# MCU_DBG.net
KiCad netlist of a schematic drawn in Altium Designer
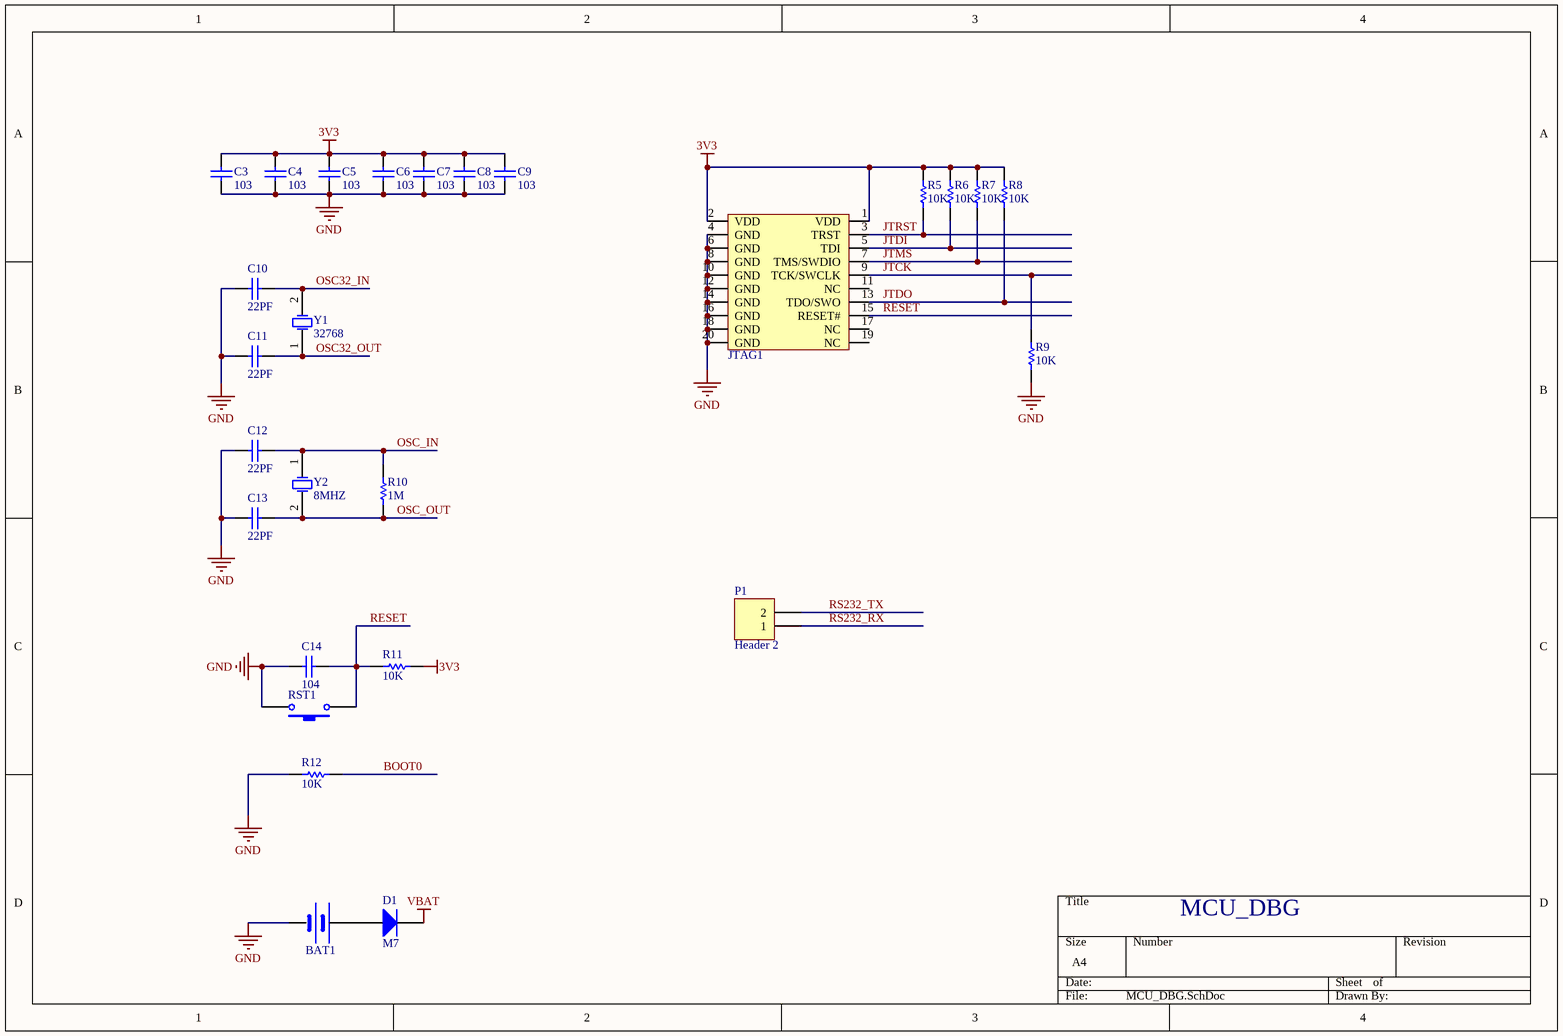
[diagram p0: MCU_DBG.SchDoc]

(export (version "E")
  (design (tool "Eeschema 10.0.6"))
  (components
    (comp (ref "BAT1")
      (value "BATT")
      (footprint "Bat2032")
      (libsource (lib "Integrated_Library_YZ") (part "BAT"))
    )
    (comp (ref "C3")
      (value "103")
      (footprint "RC0805")
      (description "Capacitor")
      (fields (field (name "Comment") "Cap") (field (name "PUBLISHER") "Altium Limited"))
      (libsource (lib "Miscellaneous Devices") (part "Cap"))
    )
    (comp (ref "C4")
      (value "103")
      (footprint "RC0805")
      (description "Capacitor")
      (fields (field (name "Comment") "Cap") (field (name "PUBLISHER") "Altium Limited"))
      (libsource (lib "Miscellaneous Devices") (part "Cap"))
    )
    (comp (ref "C5")
      (value "103")
      (footprint "RC0805")
      (description "Capacitor")
      (fields (field (name "Comment") "Cap") (field (name "PUBLISHER") "Altium Limited"))
      (libsource (lib "Miscellaneous Devices") (part "Cap"))
    )
    (comp (ref "C6")
      (value "103")
      (footprint "RC0805")
      (description "Capacitor")
      (fields (field (name "Comment") "Cap") (field (name "PUBLISHER") "Altium Limited"))
      (libsource (lib "Miscellaneous Devices") (part "Cap"))
    )
    (comp (ref "C7")
      (value "103")
      (footprint "RC0805")
      (description "Capacitor")
      (fields (field (name "Comment") "Cap") (field (name "PUBLISHER") "Altium Limited"))
      (libsource (lib "Miscellaneous Devices") (part "Cap"))
    )
    (comp (ref "C8")
      (value "103")
      (footprint "RC0805")
      (description "Capacitor")
      (fields (field (name "Comment") "Cap") (field (name "PUBLISHER") "Altium Limited"))
      (libsource (lib "Miscellaneous Devices") (part "Cap"))
    )
    (comp (ref "C9")
      (value "103")
      (footprint "RC0805")
      (description "Capacitor")
      (fields (field (name "Comment") "Cap") (field (name "PUBLISHER") "Altium Limited"))
      (libsource (lib "Miscellaneous Devices") (part "Cap"))
    )
    (comp (ref "C10")
      (value "22PF")
      (footprint "RC0805")
      (description "Capacitor")
      (fields (field (name "Comment") "Cap") (field (name "PUBLISHER") "Altium Limited"))
      (libsource (lib "Miscellaneous Devices") (part "Cap"))
    )
    (comp (ref "C11")
      (value "22PF")
      (footprint "RC0805")
      (description "Capacitor")
      (fields (field (name "Comment") "Cap") (field (name "PUBLISHER") "Altium Limited"))
      (libsource (lib "Miscellaneous Devices") (part "Cap"))
    )
    (comp (ref "C12")
      (value "22PF")
      (footprint "RC0805")
      (description "Capacitor")
      (fields (field (name "Comment") "Cap") (field (name "PUBLISHER") "Altium Limited"))
      (libsource (lib "Miscellaneous Devices") (part "Cap"))
    )
    (comp (ref "C13")
      (value "22PF")
      (footprint "RC0805")
      (description "Capacitor")
      (fields (field (name "Comment") "Cap") (field (name "PUBLISHER") "Altium Limited"))
      (libsource (lib "Miscellaneous Devices") (part "Cap"))
    )
    (comp (ref "C14")
      (value "104")
      (footprint "RC0805")
      (description "Capacitor")
      (fields (field (name "Comment") "Cap") (field (name "PUBLISHER") "Altium Limited"))
      (libsource (lib "Miscellaneous Devices") (part "Cap"))
    )
    (comp (ref "D1")
      (value "M7")
      (footprint "ss14")
      (description "Default Diode")
      (fields (field (name "PUBLISHER") "Altium Limited"))
      (libsource (lib "Miscellaneous Devices") (part "Diode"))
    )
    (comp (ref "JTAG1") (value "JTAG") (footprint "JTAG_20") (libsource (lib "底板封装库") (part "JTAG")))
    (comp (ref "P1")
      (value "Header 2")
      (footprint "HDR1X2")
      (description "Header, 2-Pin")
      (fields (field (name "PUBLISHER") "Altium Limited"))
      (libsource (lib "Miscellaneous Connectors") (part "Header 2"))
    )
    (comp (ref "R5")
      (value "10K")
      (footprint "RC0805")
      (description "Resistor")
      (fields (field (name "Comment") "Res1") (field (name "PUBLISHER") "Altium Limited"))
      (libsource (lib "Miscellaneous Devices") (part "Res1"))
    )
    (comp (ref "R6")
      (value "10K")
      (footprint "RC0805")
      (description "Resistor")
      (fields (field (name "Comment") "Res1") (field (name "PUBLISHER") "Altium Limited"))
      (libsource (lib "Miscellaneous Devices") (part "Res1"))
    )
    (comp (ref "R7")
      (value "10K")
      (footprint "RC0805")
      (description "Resistor")
      (fields (field (name "Comment") "Res1") (field (name "PUBLISHER") "Altium Limited"))
      (libsource (lib "Miscellaneous Devices") (part "Res1"))
    )
    (comp (ref "R8")
      (value "10K")
      (footprint "RC0805")
      (description "Resistor")
      (fields (field (name "Comment") "Res1") (field (name "PUBLISHER") "Altium Limited"))
      (libsource (lib "Miscellaneous Devices") (part "Res1"))
    )
    (comp (ref "R9")
      (value "10K")
      (footprint "RC0805")
      (description "Resistor")
      (fields (field (name "Comment") "Res1") (field (name "PUBLISHER") "Altium Limited"))
      (libsource (lib "Miscellaneous Devices") (part "Res1"))
    )
    (comp (ref "R10")
      (value "1M")
      (footprint "RC0805")
      (description "Resistor")
      (fields (field (name "Comment") "Res1") (field (name "PUBLISHER") "Altium Limited"))
      (libsource (lib "Miscellaneous Devices") (part "Res1"))
    )
    (comp (ref "R11")
      (value "10K")
      (footprint "RC0805")
      (description "Resistor")
      (fields (field (name "Comment") "Res1") (field (name "PUBLISHER") "Altium Limited"))
      (libsource (lib "Miscellaneous Devices") (part "Res1"))
    )
    (comp (ref "R12")
      (value "10K")
      (footprint "RC0805")
      (description "Resistor")
      (fields (field (name "Comment") "Res1") (field (name "PUBLISHER") "Altium Limited"))
      (libsource (lib "Miscellaneous Devices") (part "Res1"))
    )
    (comp (ref "RST1")
      (value "SW-PB")
      (footprint "BBTFT43_1704:小按键")
      (description "Switch")
      (fields (field (name "PUBLISHER") "Altium Limited"))
      (libsource (lib "Miscellaneous Devices") (part "SW-PB"))
    )
    (comp (ref "Y1")
      (value "32768")
      (footprint "XTAL32")
      (description "Crystal Oscillator")
      (fields (field (name "PUBLISHER") "Altium Limited"))
      (libsource (lib "Miscellaneous Devices") (part "XTAL"))
    )
    (comp (ref "Y2")
      (value "8MHZ")
      (footprint "OSC")
      (description "Crystal Oscillator")
      (fields (field (name "PUBLISHER") "Altium Limited"))
      (libsource (lib "底板封装库") (part "XTAL"))
    )
  )
  (nets
    (net (code "1") (name "/BOOT0") (class "Default")
      (node (ref "R12") (pin "2") (pinfunction "2_2") (pintype "passive"))
    )
    (net (code "2") (name "/JTCK") (class "Default")
      (node (ref "JTAG1") (pin "9") (pinfunction "TCK/SWCLK_9") (pintype "passive"))
      (node (ref "R9") (pin "1") (pinfunction "1_1") (pintype "passive"))
    )
    (net (code "3") (name "/JTDI") (class "Default")
      (node (ref "JTAG1") (pin "5") (pinfunction "TDI_5") (pintype "passive"))
      (node (ref "R6") (pin "1") (pinfunction "1_1") (pintype "passive"))
    )
    (net (code "4") (name "/JTDO") (class "Default")
      (node (ref "JTAG1") (pin "13") (pinfunction "TDO/SWO_13") (pintype "passive"))
      (node (ref "R8") (pin "1") (pinfunction "1_1") (pintype "passive"))
    )
    (net (code "5") (name "/JTMS") (class "Default")
      (node (ref "JTAG1") (pin "7") (pinfunction "TMS/SWDIO_7") (pintype "passive"))
      (node (ref "R7") (pin "1") (pinfunction "1_1") (pintype "passive"))
    )
    (net (code "6") (name "/JTRST") (class "Default")
      (node (ref "JTAG1") (pin "3") (pinfunction "TRST_3") (pintype "passive"))
      (node (ref "R5") (pin "1") (pinfunction "1_1") (pintype "passive"))
    )
    (net (code "7") (name "/OSC32_IN") (class "Default")
      (node (ref "C10") (pin "2") (pinfunction "2_2") (pintype "passive"))
      (node (ref "Y1") (pin "2") (pinfunction "OSC2_2") (pintype "passive"))
    )
    (net (code "8") (name "/OSC32_OUT") (class "Default")
      (node (ref "C11") (pin "2") (pinfunction "2_2") (pintype "passive"))
      (node (ref "Y1") (pin "1") (pinfunction "OSC1_1") (pintype "passive"))
    )
    (net (code "9") (name "/OSC_IN") (class "Default")
      (node (ref "C12") (pin "2") (pinfunction "2_2") (pintype "passive"))
      (node (ref "R10") (pin "2") (pinfunction "2_2") (pintype "passive"))
      (node (ref "Y2") (pin "1") (pinfunction "OSC1_1") (pintype "passive"))
    )
    (net (code "10") (name "/OSC_OUT") (class "Default")
      (node (ref "C13") (pin "2") (pinfunction "2_2") (pintype "passive"))
      (node (ref "R10") (pin "1") (pinfunction "1_1") (pintype "passive"))
      (node (ref "Y2") (pin "2") (pinfunction "OSC2_2") (pintype "passive"))
    )
    (net (code "11") (name "/RESET") (class "Default")
      (node (ref "C14") (pin "1") (pinfunction "1_1") (pintype "passive"))
      (node (ref "JTAG1") (pin "15") (pinfunction "RESET#_15") (pintype "passive"))
      (node (ref "R11") (pin "1") (pinfunction "1_1") (pintype "passive"))
      (node (ref "RST1") (pin "1") (pinfunction "1_1") (pintype "passive"))
    )
    (net (code "12") (name "/RS232_RX") (class "Default")
      (node (ref "P1") (pin "1") (pinfunction "1_1") (pintype "passive"))
    )
    (net (code "13") (name "/RS232_TX") (class "Default")
      (node (ref "P1") (pin "2") (pinfunction "2_2") (pintype "passive"))
    )
    (net (code "14") (name "3V3") (class "Default")
      (node (ref "C3") (pin "1") (pinfunction "1_1") (pintype "passive"))
      (node (ref "C4") (pin "1") (pinfunction "1_1") (pintype "passive"))
      (node (ref "C5") (pin "1") (pinfunction "1_1") (pintype "passive"))
      (node (ref "C6") (pin "1") (pinfunction "1_1") (pintype "passive"))
      (node (ref "C7") (pin "1") (pinfunction "1_1") (pintype "passive"))
      (node (ref "C8") (pin "1") (pinfunction "1_1") (pintype "passive"))
      (node (ref "C9") (pin "1") (pinfunction "1_1") (pintype "passive"))
      (node (ref "JTAG1") (pin "1") (pinfunction "VDD_1") (pintype "passive"))
      (node (ref "JTAG1") (pin "2") (pinfunction "VDD_2") (pintype "passive"))
      (node (ref "R11") (pin "2") (pinfunction "2_2") (pintype "passive"))
      (node (ref "R5") (pin "2") (pinfunction "2_2") (pintype "passive"))
      (node (ref "R6") (pin "2") (pinfunction "2_2") (pintype "passive"))
      (node (ref "R7") (pin "2") (pinfunction "2_2") (pintype "passive"))
      (node (ref "R8") (pin "2") (pinfunction "2_2") (pintype "passive"))
    )
    (net (code "15") (name "GND") (class "Default")
      (node (ref "BAT1") (pin "2") (pinfunction "GND_2") (pintype "passive"))
      (node (ref "C10") (pin "1") (pinfunction "1_1") (pintype "passive"))
      (node (ref "C11") (pin "1") (pinfunction "1_1") (pintype "passive"))
      (node (ref "C12") (pin "1") (pinfunction "1_1") (pintype "passive"))
      (node (ref "C13") (pin "1") (pinfunction "1_1") (pintype "passive"))
      (node (ref "C14") (pin "2") (pinfunction "2_2") (pintype "passive"))
      (node (ref "C3") (pin "2") (pinfunction "2_2") (pintype "passive"))
      (node (ref "C4") (pin "2") (pinfunction "2_2") (pintype "passive"))
      (node (ref "C5") (pin "2") (pinfunction "2_2") (pintype "passive"))
      (node (ref "C6") (pin "2") (pinfunction "2_2") (pintype "passive"))
      (node (ref "C7") (pin "2") (pinfunction "2_2") (pintype "passive"))
      (node (ref "C8") (pin "2") (pinfunction "2_2") (pintype "passive"))
      (node (ref "C9") (pin "2") (pinfunction "2_2") (pintype "passive"))
      (node (ref "JTAG1") (pin "10") (pinfunction "GND_10") (pintype "passive"))
      (node (ref "JTAG1") (pin "12") (pinfunction "GND_12") (pintype "passive"))
      (node (ref "JTAG1") (pin "14") (pinfunction "GND_14") (pintype "passive"))
      (node (ref "JTAG1") (pin "16") (pinfunction "GND_16") (pintype "passive"))
      (node (ref "JTAG1") (pin "18") (pinfunction "GND_18") (pintype "passive"))
      (node (ref "JTAG1") (pin "20") (pinfunction "GND_20") (pintype "passive"))
      (node (ref "JTAG1") (pin "4") (pinfunction "GND_4") (pintype "passive"))
      (node (ref "JTAG1") (pin "6") (pinfunction "GND_6") (pintype "passive"))
      (node (ref "JTAG1") (pin "8") (pinfunction "GND_8") (pintype "passive"))
      (node (ref "R12") (pin "1") (pinfunction "1_1") (pintype "passive"))
      (node (ref "R9") (pin "2") (pinfunction "2_2") (pintype "passive"))
      (node (ref "RST1") (pin "2") (pinfunction "2_2") (pintype "passive"))
    )
    (net (code "16") (name "Net-(BAT1-VCC)") (class "Default")
      (node (ref "BAT1") (pin "1") (pinfunction "VCC_1") (pintype "passive"))
      (node (ref "D1") (pin "1") (pinfunction "A_1") (pintype "passive"))
    )
    (net (code "17") (name "VBAT") (class "Default")
      (node (ref "D1") (pin "2") (pinfunction "K_2") (pintype "passive"))
    )
    (net (code "18") (name "unconnected-(JTAG1-NC-Pad11)") (class "Default")
      (node (ref "JTAG1") (pin "11") (pinfunction "NC_11") (pintype "passive"))
    )
    (net (code "19") (name "unconnected-(JTAG1-NC-Pad17)") (class "Default")
      (node (ref "JTAG1") (pin "17") (pinfunction "NC_17") (pintype "passive"))
    )
    (net (code "20") (name "unconnected-(JTAG1-NC-Pad19)") (class "Default")
      (node (ref "JTAG1") (pin "19") (pinfunction "NC_19") (pintype "passive"))
    )
  )
)
